# nrf24_tiny84.net
KiCad netlist of a schematic drawn in EAGLE
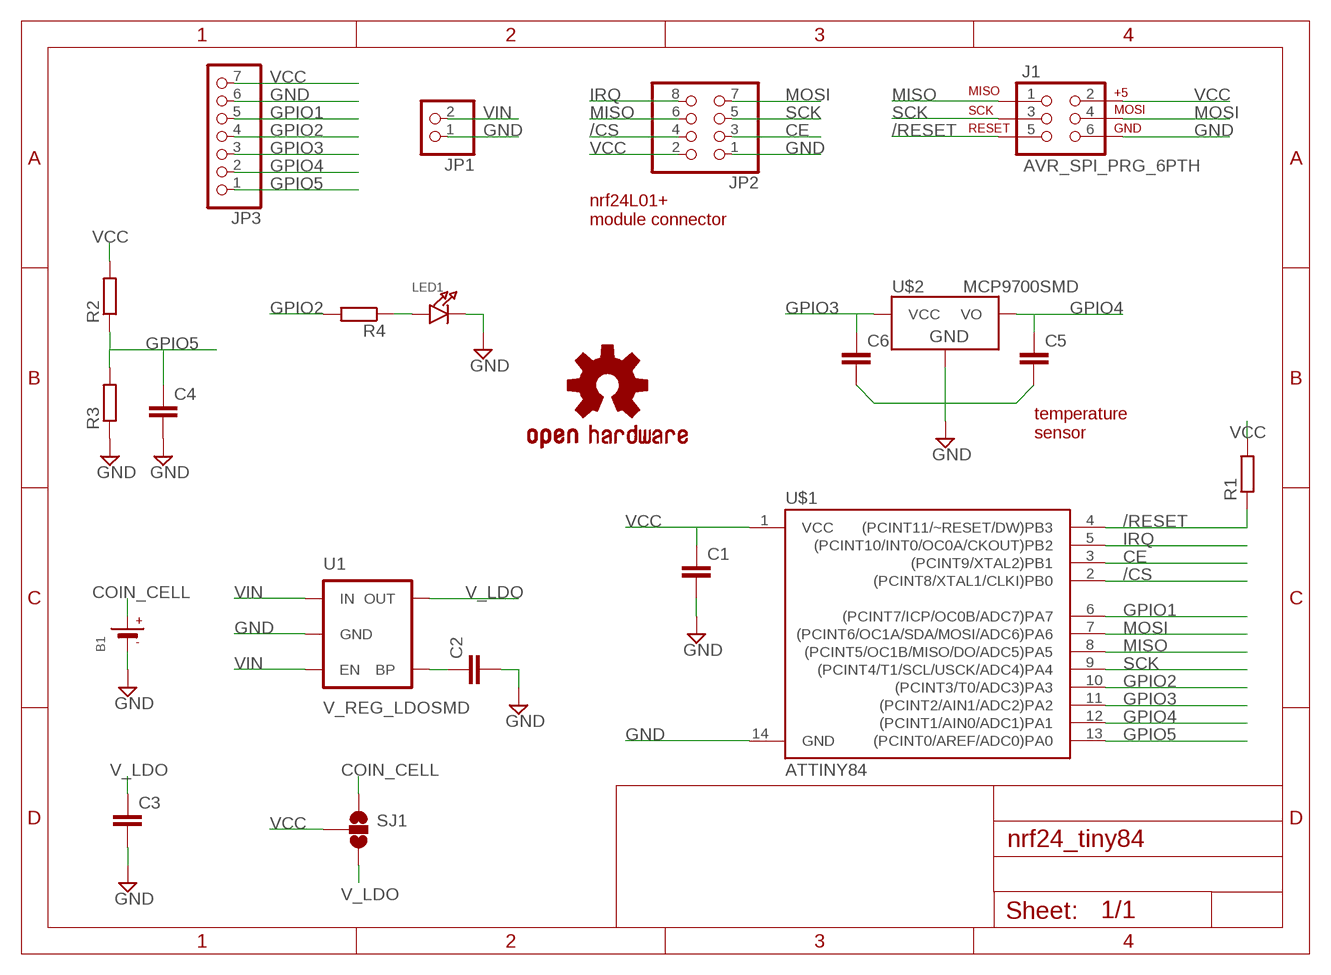
[diagram p0: schematic, sheet 1]

(export (version "E")
  (design (tool "Eeschema 10.0.6"))
  (components
    (comp (ref "B1")
      (value "BATTERYCR2032")
      (footprint "eagle-import:CR2032")
      (libsource (lib "eagle-import") (part "BATTERYCR2032"))
    )
    (comp (ref "C1")
      (value "C-EUC0805")
      (footprint "eagle-import:C0805")
      (libsource (lib "eagle-import") (part "C-EUC0805"))
    )
    (comp (ref "C2")
      (value "C-EUC0805")
      (footprint "eagle-import:C0805")
      (libsource (lib "eagle-import") (part "C-EUC0805"))
    )
    (comp (ref "C3")
      (value "C-EUC0805")
      (footprint "eagle-import:C0805")
      (libsource (lib "eagle-import") (part "C-EUC0805"))
    )
    (comp (ref "C4")
      (value "C-EUC0805")
      (footprint "eagle-import:C0805")
      (libsource (lib "eagle-import") (part "C-EUC0805"))
    )
    (comp (ref "C5")
      (value "C-EUC0805")
      (footprint "eagle-import:C0805")
      (libsource (lib "eagle-import") (part "C-EUC0805"))
    )
    (comp (ref "C6")
      (value "C-EUC0805")
      (footprint "eagle-import:C0805")
      (libsource (lib "eagle-import") (part "C-EUC0805"))
    )
    (comp (ref "J1")
      (value "AVR_SPI_PRG_6PTH")
      (footprint "eagle-import:2X3")
      (libsource (lib "eagle-import") (part "AVR_SPI_PRG_6PTH"))
    )
    (comp (ref "JP1")
      (value "HEADER-1X2ROUND")
      (footprint "eagle-import:1X02_ROUND")
      (libsource (lib "eagle-import") (part "HEADER-1X2ROUND"))
    )
    (comp (ref "JP2")
      (value "PINHD-2X4")
      (footprint "eagle-import:2X04")
      (libsource (lib "eagle-import") (part "PINHD-2X4"))
    )
    (comp (ref "JP3")
      (value "HEADER-1X7ROUND")
      (footprint "eagle-import:1X07_ROUND")
      (libsource (lib "eagle-import") (part "HEADER-1X7ROUND"))
    )
    (comp (ref "LED1")
      (value "LED0805")
      (footprint "eagle-import:CHIPLED_0805")
      (libsource (lib "eagle-import") (part "LED0805"))
    )
    (comp (ref "LOGO1")
      (value "OSHW-LOGOS")
      (footprint "eagle-import:OSHW-LOGO-S")
      (libsource (lib "eagle-import") (part "OSHW-LOGOS"))
    )
    (comp (ref "R1")
      (value "R-EU_R0805")
      (footprint "eagle-import:R0805")
      (libsource (lib "eagle-import") (part "R-EU_R0805"))
    )
    (comp (ref "R2")
      (value "R-EU_R0805")
      (footprint "eagle-import:R0805")
      (libsource (lib "eagle-import") (part "R-EU_R0805"))
    )
    (comp (ref "R3")
      (value "R-EU_R0805")
      (footprint "eagle-import:R0805")
      (libsource (lib "eagle-import") (part "R-EU_R0805"))
    )
    (comp (ref "R4")
      (value "R-EU_R0805")
      (footprint "eagle-import:R0805")
      (libsource (lib "eagle-import") (part "R-EU_R0805"))
    )
    (comp (ref "SJ1")
      (value "SOLDERJUMPER_2WAYS")
      (footprint "eagle-import:SJ_3")
      (libsource (lib "eagle-import") (part "SOLDERJUMPER_2WAYS"))
    )
    (comp (ref "U$1")
      (value "ATTINY84")
      (footprint "eagle-import:SO14")
      (libsource (lib "eagle-import") (part "ATTINY84"))
    )
    (comp (ref "U$2")
      (value "MCP9700SMD")
      (footprint "eagle-import:SOT23-3")
      (libsource (lib "eagle-import") (part "MCP9700SMD"))
    )
    (comp (ref "U1")
      (value "V_REG_LDOSMD")
      (footprint "eagle-import:SOT23-5")
      (libsource (lib "eagle-import") (part "V_REG_LDOSMD"))
    )
  )
  (nets
    (net (code "1") (name "/CE") (class "Default")
      (node (ref "JP2") (pin "3") (pinfunction "3_3") (pintype "passive"))
      (node (ref "U$1") (pin "3") (pinfunction "(PCINT9/XTAL2)PB1_3") (pintype "bidirectional"))
    )
    (net (code "2") (name "/COIN_CELL") (class "Default")
      (node (ref "B1") (pin "+") (pinfunction "+_+") (pintype "passive"))
      (node (ref "SJ1") (pin "1") (pinfunction "1_1") (pintype "passive"))
    )
    (net (code "3") (name "/GPIO1") (class "Default")
      (node (ref "JP3") (pin "5") (pinfunction "5_5") (pintype "passive"))
      (node (ref "U$1") (pin "6") (pinfunction "(PCINT7/ICP/OC0B/ADC7)PA7_6") (pintype "bidirectional"))
    )
    (net (code "4") (name "/GPIO2") (class "Default")
      (node (ref "JP3") (pin "4") (pinfunction "4_4") (pintype "passive"))
      (node (ref "R4") (pin "2") (pinfunction "2_2") (pintype "passive"))
      (node (ref "U$1") (pin "10") (pinfunction "(PCINT3/T0/ADC3)PA3_10") (pintype "bidirectional"))
    )
    (net (code "5") (name "/GPIO3") (class "Default")
      (node (ref "C6") (pin "1") (pinfunction "1_1") (pintype "passive"))
      (node (ref "JP3") (pin "3") (pinfunction "3_3") (pintype "passive"))
      (node (ref "U$1") (pin "11") (pinfunction "(PCINT2/AIN1/ADC2)PA2_11") (pintype "bidirectional"))
      (node (ref "U$2") (pin "1") (pinfunction "VCC_1") (pintype "bidirectional"))
    )
    (net (code "6") (name "/GPIO4") (class "Default")
      (node (ref "C5") (pin "1") (pinfunction "1_1") (pintype "passive"))
      (node (ref "JP3") (pin "2") (pinfunction "2_2") (pintype "passive"))
      (node (ref "U$1") (pin "12") (pinfunction "(PCINT1/AIN0/ADC1)PA1_12") (pintype "bidirectional"))
      (node (ref "U$2") (pin "2") (pinfunction "VO_2") (pintype "bidirectional"))
    )
    (net (code "7") (name "/GPIO5") (class "Default")
      (node (ref "C4") (pin "1") (pinfunction "1_1") (pintype "passive"))
      (node (ref "JP3") (pin "1") (pinfunction "1_1") (pintype "passive"))
      (node (ref "R2") (pin "1") (pinfunction "1_1") (pintype "passive"))
      (node (ref "R3") (pin "2") (pinfunction "2_2") (pintype "passive"))
      (node (ref "U$1") (pin "13") (pinfunction "(PCINT0/AREF/ADC0)PA0_13") (pintype "bidirectional"))
    )
    (net (code "8") (name "/IRQ") (class "Default")
      (node (ref "JP2") (pin "8") (pinfunction "8_8") (pintype "passive"))
      (node (ref "U$1") (pin "5") (pinfunction "(PCINT10/INT0/OC0A/CKOUT)PB2_5") (pintype "bidirectional"))
    )
    (net (code "9") (name "/MISO") (class "Default")
      (node (ref "J1") (pin "1") (pinfunction "1_1") (pintype "passive"))
      (node (ref "JP2") (pin "6") (pinfunction "6_6") (pintype "passive"))
      (node (ref "U$1") (pin "8") (pinfunction "(PCINT5/OC1B/MISO/DO/ADC5)PA5_8") (pintype "bidirectional"))
    )
    (net (code "10") (name "/MOSI") (class "Default")
      (node (ref "J1") (pin "4") (pinfunction "4_4") (pintype "passive"))
      (node (ref "JP2") (pin "7") (pinfunction "7_7") (pintype "passive"))
      (node (ref "U$1") (pin "7") (pinfunction "(PCINT6/OC1A/SDA/MOSI/ADC6)PA6_7") (pintype "bidirectional"))
    )
    (net (code "11") (name "/SCK") (class "Default")
      (node (ref "J1") (pin "3") (pinfunction "3_3") (pintype "passive"))
      (node (ref "JP2") (pin "5") (pinfunction "5_5") (pintype "passive"))
      (node (ref "U$1") (pin "9") (pinfunction "(PCINT4/T1/SCL/USCK/ADC4)PA4_9") (pintype "bidirectional"))
    )
    (net (code "12") (name "/VCC") (class "Default")
      (node (ref "C1") (pin "1") (pinfunction "1_1") (pintype "passive"))
      (node (ref "J1") (pin "2") (pinfunction "2_2") (pintype "passive"))
      (node (ref "JP2") (pin "2") (pinfunction "2_2") (pintype "passive"))
      (node (ref "JP3") (pin "7") (pinfunction "7_7") (pintype "passive"))
      (node (ref "R1") (pin "2") (pinfunction "2_2") (pintype "passive"))
      (node (ref "R2") (pin "2") (pinfunction "2_2") (pintype "passive"))
      (node (ref "SJ1") (pin "2") (pinfunction "2_2") (pintype "passive"))
      (node (ref "U$1") (pin "1") (pinfunction "VCC_1") (pintype "bidirectional"))
    )
    (net (code "13") (name "/VIN") (class "Default")
      (node (ref "JP1") (pin "2") (pinfunction "2_2") (pintype "passive"))
      (node (ref "U1") (pin "1") (pinfunction "IN_1") (pintype "input"))
      (node (ref "U1") (pin "3") (pinfunction "EN_3") (pintype "input"))
    )
    (net (code "14") (name "/V_LDO") (class "Default")
      (node (ref "C3") (pin "1") (pinfunction "1_1") (pintype "passive"))
      (node (ref "SJ1") (pin "3") (pinfunction "3_3") (pintype "passive"))
      (node (ref "U1") (pin "5") (pinfunction "OUT_5") (pintype "passive"))
    )
    (net (code "15") (name "/{slash}CS") (class "Default")
      (node (ref "JP2") (pin "4") (pinfunction "4_4") (pintype "passive"))
      (node (ref "U$1") (pin "2") (pinfunction "(PCINT8/XTAL1/CLKI)PB0_2") (pintype "bidirectional"))
    )
    (net (code "16") (name "/{slash}RESET") (class "Default")
      (node (ref "J1") (pin "5") (pinfunction "5_5") (pintype "passive"))
      (node (ref "R1") (pin "1") (pinfunction "1_1") (pintype "passive"))
      (node (ref "U$1") (pin "4") (pinfunction "(PCINT11/~{RESET/DW})PB3_4") (pintype "bidirectional"))
    )
    (net (code "17") (name "GND") (class "Default")
      (node (ref "B1") (pin "-") (pinfunction "-_-") (pintype "passive"))
      (node (ref "C1") (pin "2") (pinfunction "2_2") (pintype "passive"))
      (node (ref "C2") (pin "2") (pinfunction "2_2") (pintype "passive"))
      (node (ref "C3") (pin "2") (pinfunction "2_2") (pintype "passive"))
      (node (ref "C4") (pin "2") (pinfunction "2_2") (pintype "passive"))
      (node (ref "C5") (pin "2") (pinfunction "2_2") (pintype "passive"))
      (node (ref "C6") (pin "2") (pinfunction "2_2") (pintype "passive"))
      (node (ref "J1") (pin "6") (pinfunction "6_6") (pintype "passive"))
      (node (ref "JP1") (pin "1") (pinfunction "1_1") (pintype "passive"))
      (node (ref "JP2") (pin "1") (pinfunction "1_1") (pintype "passive"))
      (node (ref "JP3") (pin "6") (pinfunction "6_6") (pintype "passive"))
      (node (ref "LED1") (pin "C") (pinfunction "C_C") (pintype "passive"))
      (node (ref "R3") (pin "1") (pinfunction "1_1") (pintype "passive"))
      (node (ref "U$1") (pin "14") (pinfunction "GND_14") (pintype "bidirectional"))
      (node (ref "U$2") (pin "3") (pinfunction "GND_3") (pintype "bidirectional"))
      (node (ref "U1") (pin "2") (pinfunction "GND_2") (pintype "input"))
    )
    (net (code "18") (name "Net-(LED1-PadA)") (class "Default")
      (node (ref "LED1") (pin "A") (pinfunction "A_A") (pintype "passive"))
      (node (ref "R4") (pin "1") (pinfunction "1_1") (pintype "passive"))
    )
    (net (code "19") (name "Net-(U1-BP)") (class "Default")
      (node (ref "C2") (pin "1") (pinfunction "1_1") (pintype "passive"))
      (node (ref "U1") (pin "4") (pinfunction "BP_4") (pintype "input"))
    )
  )
)
